# SUBBOARD-sensors.net
KiCad netlist of a schematic drawn in Altium Designer
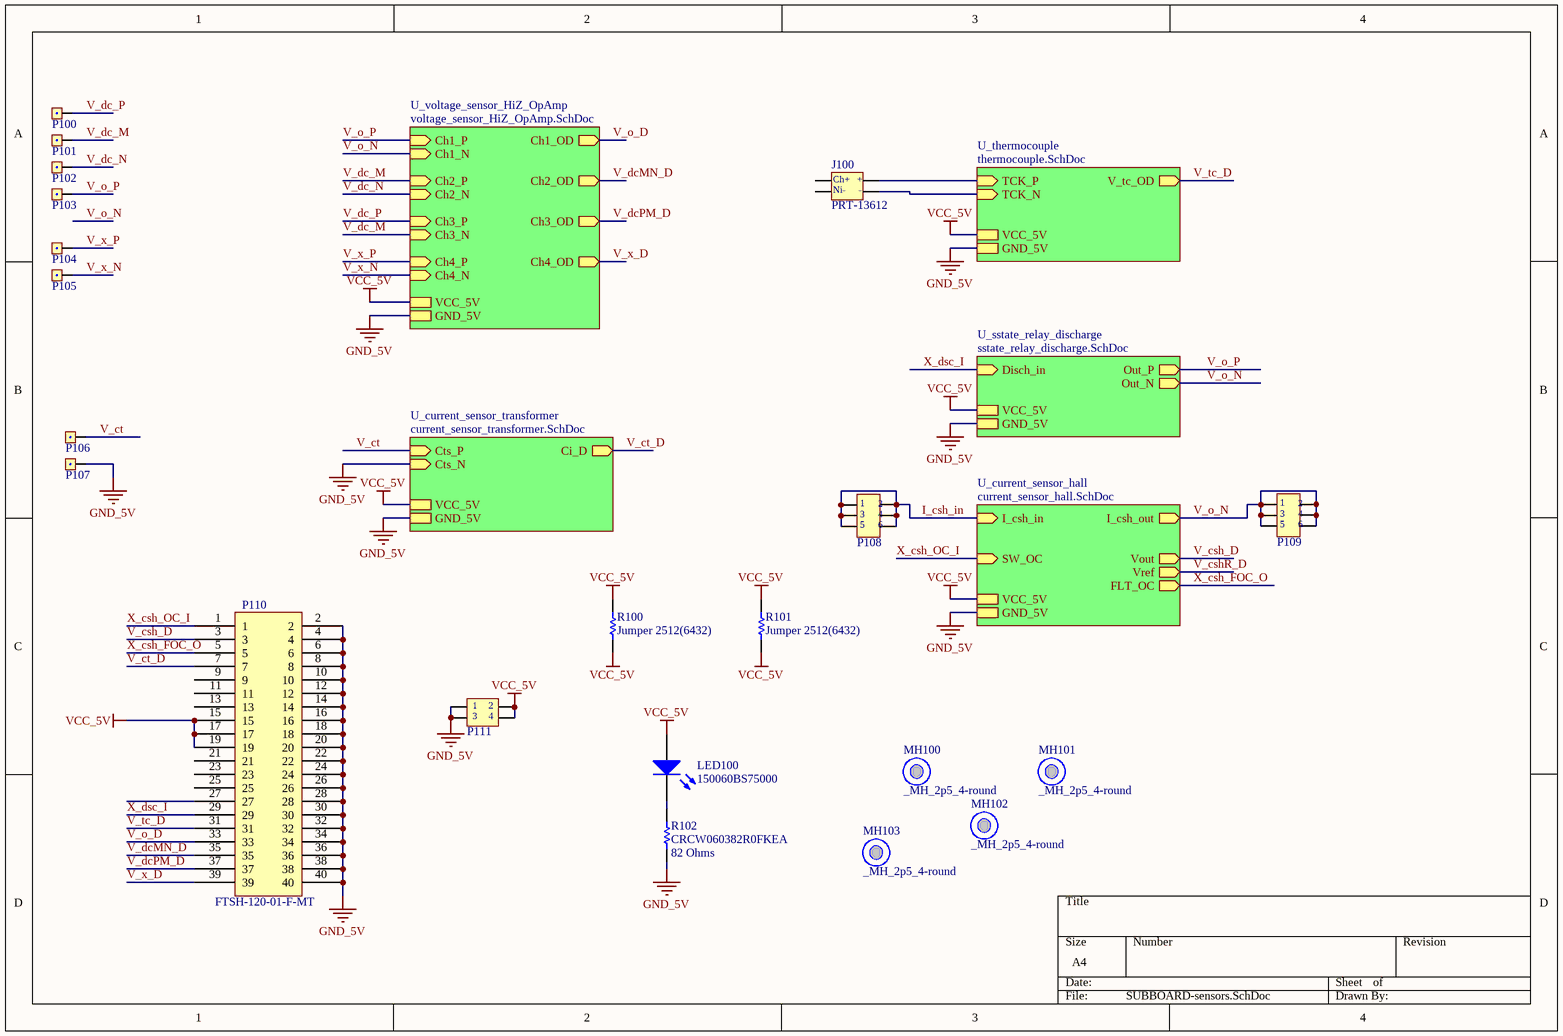
[diagram p0: SUBBOARD-sensors.SchDoc]

(export (version "E")
  (design (tool "Eeschema 10.0.6"))
  (components
    (comp (ref "J100")
      (value "PRT-13612")
      (footprint "PRT-13612")
      (description "THERMOCOUPLE CONN - PCC-SMP-K")
      (fields (field (name "MANUFACTURER") "SparkFun"))
      (libsource (lib "Altium_Library_POWERLAB") (part "PRT-13612"))
    )
    (comp (ref "LED100")
      (value "150060BS75000")
      (footprint "0603_A")
      (description "SMD mono-color Chip LED, WL-SMCW, Blue")
      (fields (field (name "MANUFACTURER") "Wuerth Elektronik"))
      (libsource (lib "Altium Content Vault") (part "WE-LED_K1A2-2"))
    )
    (comp (ref "MH100")
      (value "_MH_2p5_4-round")
      (footprint "_MH_2p5_4-round")
      (description "matching hole 2.5 hole, 4mm pad (round)")
      (libsource (lib "Altium_Library_POWERLAB") (part "_MH_2p5_4-round"))
    )
    (comp (ref "MH101")
      (value "_MH_2p5_4-round")
      (footprint "_MH_2p5_4-round")
      (description "matching hole 2.5 hole, 4mm pad (round)")
      (libsource (lib "Altium_Library_POWERLAB") (part "_MH_2p5_4-round"))
    )
    (comp (ref "MH102")
      (value "_MH_2p5_4-round")
      (footprint "_MH_2p5_4-round")
      (description "matching hole 2.5 hole, 4mm pad (round)")
      (libsource (lib "Altium_Library_POWERLAB") (part "_MH_2p5_4-round"))
    )
    (comp (ref "MH103")
      (value "_MH_2p5_4-round")
      (footprint "_MH_2p5_4-round")
      (description "matching hole 2.5 hole, 4mm pad (round)")
      (libsource (lib "Altium_Library_POWERLAB") (part "_MH_2p5_4-round"))
    )
    (comp (ref "P100")
      (value "TSW-101-15-G-S")
      (footprint "TSW-101-15-G-S")
      (description "Conn Unshrouded Header HDR 1 POS Solder ST Thru-Hole")
      (fields (field (name "MANUFACTURER") "Samtec"))
      (libsource (lib "Altium_Library_POWERLAB") (part "TSW-101-15-G-S"))
    )
    (comp (ref "P101")
      (value "TSW-101-15-G-S")
      (footprint "TSW-101-15-G-S")
      (description "Conn Unshrouded Header HDR 1 POS Solder ST Thru-Hole")
      (fields (field (name "MANUFACTURER") "Samtec"))
      (libsource (lib "Altium_Library_POWERLAB") (part "TSW-101-15-G-S"))
    )
    (comp (ref "P102")
      (value "TSW-101-15-G-S")
      (footprint "TSW-101-15-G-S")
      (description "Conn Unshrouded Header HDR 1 POS Solder ST Thru-Hole")
      (fields (field (name "MANUFACTURER") "Samtec"))
      (libsource (lib "Altium_Library_POWERLAB") (part "TSW-101-15-G-S"))
    )
    (comp (ref "P103")
      (value "TSW-101-15-G-S")
      (footprint "TSW-101-15-G-S")
      (description "Conn Unshrouded Header HDR 1 POS Solder ST Thru-Hole")
      (fields (field (name "MANUFACTURER") "Samtec"))
      (libsource (lib "Altium_Library_POWERLAB") (part "TSW-101-15-G-S"))
    )
    (comp (ref "P104")
      (value "TSW-101-15-G-S")
      (footprint "TSW-101-15-G-S")
      (description "Conn Unshrouded Header HDR 1 POS Solder ST Thru-Hole")
      (fields (field (name "MANUFACTURER") "Samtec"))
      (libsource (lib "Altium_Library_POWERLAB") (part "TSW-101-15-G-S"))
    )
    (comp (ref "P105")
      (value "TSW-101-15-G-S")
      (footprint "TSW-101-15-G-S")
      (description "Conn Unshrouded Header HDR 1 POS Solder ST Thru-Hole")
      (fields (field (name "MANUFACTURER") "Samtec"))
      (libsource (lib "Altium_Library_POWERLAB") (part "TSW-101-15-G-S"))
    )
    (comp (ref "P106")
      (value "TSW-101-15-G-S")
      (footprint "TSW-101-15-G-S")
      (description "Conn Unshrouded Header HDR 1 POS Solder ST Thru-Hole")
      (fields (field (name "MANUFACTURER") "Samtec"))
      (libsource (lib "Altium_Library_POWERLAB") (part "TSW-101-15-G-S"))
    )
    (comp (ref "P107")
      (value "TSW-101-15-G-S")
      (footprint "TSW-101-15-G-S")
      (description "Conn Unshrouded Header HDR 1 POS Solder ST Thru-Hole")
      (fields (field (name "MANUFACTURER") "Samtec"))
      (libsource (lib "Altium_Library_POWERLAB") (part "TSW-101-15-G-S"))
    )
    (comp (ref "P108")
      (value "TSW-103-15-G-D")
      (footprint "TSW-103-15-G-D")
      (description ".025\" SQ. TERMINAL STRIPS")
      (fields (field (name "MANUFACTURER") "Samtec"))
      (libsource (lib "Altium_Library_POWERLAB") (part "TSW-103-15-G-D"))
    )
    (comp (ref "P109")
      (value "TSW-103-15-G-D")
      (footprint "TSW-103-15-G-D")
      (description ".025\" SQ. TERMINAL STRIPS")
      (fields (field (name "MANUFACTURER") "Samtec"))
      (libsource (lib "Altium_Library_POWERLAB") (part "TSW-103-15-G-D"))
    )
    (comp (ref "P110")
      (value "FTSH-120-01-F-MT")
      (footprint "FTSH-120-01-F-MT")
      (description "Conn Unshrouded Header HDR 40 POS 1.27mm Solder RA Thru-Hole/SMD Tube")
      (fields (field (name "MANUFACTURER") "Samtec"))
      (libsource (lib "Altium_Library_POWERLAB") (part "FTSH-120-01-F-MT"))
    )
    (comp (ref "P111")
      (value "TMM-102-02-T-D")
      (footprint "TMM-102-02-T-D")
      (fields (field (name "MANUFACTURER") "Samtec"))
      (libsource (lib "Altium_Library_POWERLAB") (part "TMM-102-02-T-D"))
    )
    (comp (ref "R100")
      (value "Jumper 2512(6432)")
      (footprint "RESC2512(6432)_L")
      (description "Jumper 2512 (6432 Metric)")
      (fields (field (name "TOLERANCE") "None"))
      (libsource (lib "Altium Content Vault") (part "RES"))
    )
    (comp (ref "R101")
      (value "Jumper 2512(6432)")
      (footprint "RESC2512(6432)_L")
      (description "Jumper 2512 (6432 Metric)")
      (fields (field (name "TOLERANCE") "None"))
      (libsource (lib "Altium Content Vault") (part "RES"))
    )
    (comp (ref "R102")
      (value "CRCW060382R0FKEA")
      (footprint "RESC1609X50X30LL10T20")
      (fields (field (name "MANUFACTURER") "Vishay Dale") (field (name "ALTIUM_VALUE") "82 Ohms"))
      (libsource (lib "Altium Content Vault") (part "RES"))
    )
  )
  (nets
    (net (code "1") (name "/I_csh_in") (class "Default")
      (node (ref "P108") (pin "1") (pinfunction "1_1") (pintype "passive"))
      (node (ref "P108") (pin "2") (pinfunction "2_2") (pintype "passive"))
      (node (ref "P108") (pin "3") (pinfunction "3_3") (pintype "passive"))
      (node (ref "P108") (pin "4") (pinfunction "4_4") (pintype "passive"))
      (node (ref "P108") (pin "5") (pinfunction "5_5") (pintype "passive"))
      (node (ref "P108") (pin "6") (pinfunction "6_6") (pintype "passive"))
    )
    (net (code "2") (name "/TCK_N") (class "Default")
      (node (ref "J100") (pin "4") (pinfunction "4_4") (pintype "passive"))
    )
    (net (code "3") (name "/TCK_P") (class "Default")
      (node (ref "J100") (pin "3") (pinfunction "3_3") (pintype "passive"))
    )
    (net (code "5") (name "/V_csh_D") (class "Default")
      (node (ref "P110") (pin "3") (pinfunction "3_3") (pintype "passive"))
    )
    (net (code "6") (name "/V_ct") (class "Default")
      (node (ref "P106") (pin "1") (pinfunction "1_1") (pintype "passive"))
    )
    (net (code "7") (name "/V_ct_D") (class "Default")
      (node (ref "P110") (pin "7") (pinfunction "7_7") (pintype "passive"))
    )
    (net (code "8") (name "/V_dcMN_D") (class "Default")
      (node (ref "P110") (pin "35") (pinfunction "35_35") (pintype "passive"))
    )
    (net (code "9") (name "/V_dcPM_D") (class "Default")
      (node (ref "P110") (pin "37") (pinfunction "37_37") (pintype "passive"))
    )
    (net (code "10") (name "/V_dc_M") (class "Default")
      (node (ref "P101") (pin "1") (pinfunction "1_1") (pintype "passive"))
    )
    (net (code "11") (name "/V_dc_N") (class "Default")
      (node (ref "P102") (pin "1") (pinfunction "1_1") (pintype "passive"))
    )
    (net (code "12") (name "/V_dc_P") (class "Default")
      (node (ref "P100") (pin "1") (pinfunction "1_1") (pintype "passive"))
    )
    (net (code "13") (name "/V_o_D") (class "Default")
      (node (ref "P110") (pin "33") (pinfunction "33_33") (pintype "passive"))
    )
    (net (code "14") (name "/V_o_N") (class "Default")
      (node (ref "P109") (pin "1") (pinfunction "1_1") (pintype "passive"))
      (node (ref "P109") (pin "2") (pinfunction "2_2") (pintype "passive"))
      (node (ref "P109") (pin "3") (pinfunction "3_3") (pintype "passive"))
      (node (ref "P109") (pin "4") (pinfunction "4_4") (pintype "passive"))
      (node (ref "P109") (pin "5") (pinfunction "5_5") (pintype "passive"))
      (node (ref "P109") (pin "6") (pinfunction "6_6") (pintype "passive"))
    )
    (net (code "15") (name "/V_o_P") (class "Default")
      (node (ref "P103") (pin "1") (pinfunction "1_1") (pintype "passive"))
    )
    (net (code "16") (name "/V_tc_D") (class "Default")
      (node (ref "P110") (pin "31") (pinfunction "31_31") (pintype "passive"))
    )
    (net (code "17") (name "/V_x_D") (class "Default")
      (node (ref "P110") (pin "39") (pinfunction "39_39") (pintype "passive"))
    )
    (net (code "18") (name "/V_x_N") (class "Default")
      (node (ref "P105") (pin "1") (pinfunction "1_1") (pintype "passive"))
    )
    (net (code "19") (name "/V_x_P") (class "Default")
      (node (ref "P104") (pin "1") (pinfunction "1_1") (pintype "passive"))
    )
    (net (code "20") (name "/X_csh_FOC_O") (class "Default")
      (node (ref "P110") (pin "5") (pinfunction "5_5") (pintype "passive"))
    )
    (net (code "21") (name "/X_csh_OC_I") (class "Default")
      (node (ref "P110") (pin "1") (pinfunction "1_1") (pintype "passive"))
    )
    (net (code "22") (name "/X_dsc_I") (class "Default")
      (node (ref "P110") (pin "29") (pinfunction "29_29") (pintype "passive"))
    )
    (net (code "23") (name "GND_5V") (class "Default")
      (node (ref "P107") (pin "1") (pinfunction "1_1") (pintype "passive"))
      (node (ref "P110") (pin "10") (pinfunction "10_10") (pintype "passive"))
      (node (ref "P110") (pin "12") (pinfunction "12_12") (pintype "passive"))
      (node (ref "P110") (pin "14") (pinfunction "14_14") (pintype "passive"))
      (node (ref "P110") (pin "16") (pinfunction "16_16") (pintype "passive"))
      (node (ref "P110") (pin "18") (pinfunction "18_18") (pintype "passive"))
      (node (ref "P110") (pin "2") (pinfunction "2_2") (pintype "passive"))
      (node (ref "P110") (pin "20") (pinfunction "20_20") (pintype "passive"))
      (node (ref "P110") (pin "22") (pinfunction "22_22") (pintype "passive"))
      (node (ref "P110") (pin "24") (pinfunction "24_24") (pintype "passive"))
      (node (ref "P110") (pin "26") (pinfunction "26_26") (pintype "passive"))
      (node (ref "P110") (pin "28") (pinfunction "28_28") (pintype "passive"))
      (node (ref "P110") (pin "30") (pinfunction "30_30") (pintype "passive"))
      (node (ref "P110") (pin "32") (pinfunction "32_32") (pintype "passive"))
      (node (ref "P110") (pin "34") (pinfunction "34_34") (pintype "passive"))
      (node (ref "P110") (pin "36") (pinfunction "36_36") (pintype "passive"))
      (node (ref "P110") (pin "38") (pinfunction "38_38") (pintype "passive"))
      (node (ref "P110") (pin "4") (pinfunction "4_4") (pintype "passive"))
      (node (ref "P110") (pin "40") (pinfunction "40_40") (pintype "passive"))
      (node (ref "P110") (pin "6") (pinfunction "6_6") (pintype "passive"))
      (node (ref "P110") (pin "8") (pinfunction "8_8") (pintype "passive"))
      (node (ref "P111") (pin "1") (pinfunction "1_1") (pintype "passive"))
      (node (ref "P111") (pin "3") (pinfunction "3_3") (pintype "passive"))
      (node (ref "R102") (pin "2") (pinfunction "2_2") (pintype "passive"))
    )
    (net (code "24") (name "Net-(LED100-K)") (class "Default")
      (node (ref "LED100") (pin "1") (pinfunction "K_1") (pintype "passive"))
      (node (ref "R102") (pin "1") (pinfunction "1_1") (pintype "passive"))
    )
    (net (code "25") (name "VCC_5V") (class "Default")
      (node (ref "LED100") (pin "2") (pinfunction "A_2") (pintype "passive"))
      (node (ref "P110") (pin "15") (pinfunction "15_15") (pintype "passive"))
      (node (ref "P110") (pin "17") (pinfunction "17_17") (pintype "passive"))
      (node (ref "P110") (pin "19") (pinfunction "19_19") (pintype "passive"))
      (node (ref "P111") (pin "2") (pinfunction "2_2") (pintype "passive"))
      (node (ref "P111") (pin "4") (pinfunction "4_4") (pintype "passive"))
      (node (ref "R100") (pin "1") (pinfunction "1_1") (pintype "passive"))
      (node (ref "R100") (pin "2") (pinfunction "2_2") (pintype "passive"))
      (node (ref "R101") (pin "1") (pinfunction "1_1") (pintype "passive"))
      (node (ref "R101") (pin "2") (pinfunction "2_2") (pintype "passive"))
    )
    (net (code "26") (name "unconnected-(J100-Pad1)") (class "Default")
      (node (ref "J100") (pin "1") (pinfunction "1_1") (pintype "passive"))
    )
    (net (code "27") (name "unconnected-(J100-Pad2)") (class "Default")
      (node (ref "J100") (pin "2") (pinfunction "2_2") (pintype "passive"))
    )
    (net (code "28") (name "unconnected-(P110-Pad9)") (class "Default")
      (node (ref "P110") (pin "9") (pinfunction "9_9") (pintype "passive"))
    )
    (net (code "29") (name "unconnected-(P110-Pad11)") (class "Default")
      (node (ref "P110") (pin "11") (pinfunction "11_11") (pintype "passive"))
    )
    (net (code "30") (name "unconnected-(P110-Pad13)") (class "Default")
      (node (ref "P110") (pin "13") (pinfunction "13_13") (pintype "passive"))
    )
    (net (code "31") (name "unconnected-(P110-Pad21)") (class "Default")
      (node (ref "P110") (pin "21") (pinfunction "21_21") (pintype "passive"))
    )
    (net (code "32") (name "unconnected-(P110-Pad23)") (class "Default")
      (node (ref "P110") (pin "23") (pinfunction "23_23") (pintype "passive"))
    )
    (net (code "33") (name "unconnected-(P110-Pad25)") (class "Default")
      (node (ref "P110") (pin "25") (pinfunction "25_25") (pintype "passive"))
    )
    (net (code "34") (name "unconnected-(P110-Pad27)") (class "Default")
      (node (ref "P110") (pin "27") (pinfunction "27_27") (pintype "passive"))
    )
  )
)
